# DataDriven_sheet3_power_supply.net
KiCad netlist of a schematic drawn in Altium Designer
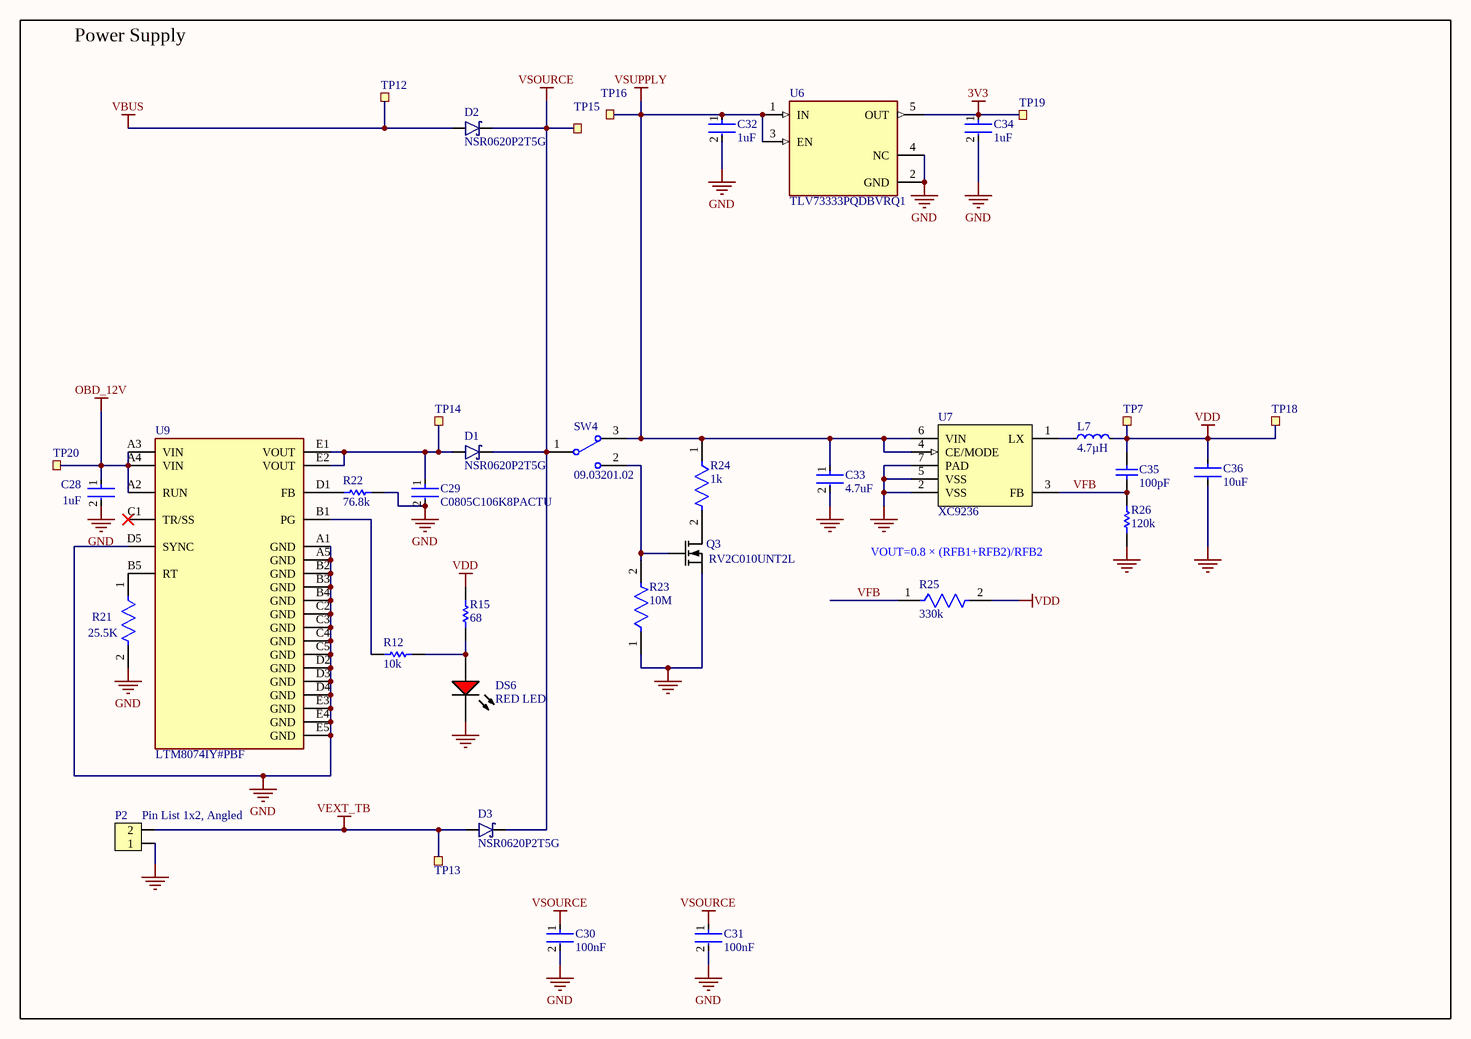
[diagram p0: DataDriven_sheet3_power_supply.SchDoc]

(export (version "E")
  (design (tool "Eeschema 10.0.6"))
  (components
    (comp (ref "C28")
      (value "1uF")
      (footprint "FP-0603-L_1_6_0_1-W_0_8_0-IPC_A")
      (description "1 µF ±10% 50V Ceramic Capacitor X5R 0603 (1608 Metric)")
      (fields (field (name "TOLERANCE") "10%") (field (name "MANUFACTURER") "Taiyo Yuden"))
      (libsource (lib "Altium Content Vault") (part "02cd4be3c70576c341d710602a673aa"))
    )
    (comp (ref "C29")
      (value "C0805C106K8PACTU")
      (footprint "FP-C0805C-DG-MFG")
      (description "CAP CER 10UF 10V X5R 0805")
      (fields (field (name "TOLERANCE") "10%") (field (name "MANUFACTURER") "Kemet"))
      (libsource (lib "Altium Content Vault") (part "11868f565c42a9108669ba33697ecf6"))
    )
    (comp (ref "C30")
      (value "100nF")
      (footprint "FP-CGA3E-0_3-0_1-IPC_A")
      (description "Cap Ceramic 100nF 50V X7R 10% Pad SMD 0603 +125°C Automotive T/R")
      (fields (field (name "TOLERANCE") "10%") (field (name "VOLTAGE") "50V"))
      (libsource (lib "Altium Content Vault") (part "b4654b650e69147ec39a6b967a45e02"))
    )
    (comp (ref "C31")
      (value "100nF")
      (footprint "FP-CGA3E-0_3-0_1-IPC_A")
      (description "Cap Ceramic 100nF 50V X7R 10% Pad SMD 0603 +125°C Automotive T/R")
      (fields (field (name "TOLERANCE") "10%") (field (name "VOLTAGE") "50V"))
      (libsource (lib "Altium Content Vault") (part "b4654b650e69147ec39a6b967a45e02"))
    )
    (comp (ref "C32")
      (value "1uF")
      (footprint "FP-GRT188-0_1-e0_2_0_5-IPC_B")
      (description "Multi-Layer Ceramic Capacitor 1uF 50V X5R ±10% 0603 Paper T/R")
      (fields (field (name "TOLERANCE") "10%") (field (name "MANUFACTURER") "Murata"))
      (libsource (lib "Altium Content Vault") (part "02cd4be3c70576c341d710602a673aa"))
    )
    (comp (ref "C33")
      (value "4.7uF")
      (footprint "FP-GRM188-0_2-IPC_C")
      (description "Chip Multilayer Ceramic Capacitors for General Purpose, 0603, 4.7uF, X5R, 15%, 10%, 35V")
      (fields (field (name "VOLTAGE") "35V") (field (name "TOLERANCE") "10%"))
      (libsource (lib "Altium Content Vault") (part "11868f565c42a9108669ba33697ecf6"))
    )
    (comp (ref "C34")
      (value "1uF")
      (footprint "FP-GRT188-0_1-e0_2_0_5-IPC_B")
      (description "Multi-Layer Ceramic Capacitor 1uF 50V X5R ±10% 0603 Paper T/R")
      (fields (field (name "TOLERANCE") "10%") (field (name "MANUFACTURER") "Murata"))
      (libsource (lib "Altium Content Vault") (part "02cd4be3c70576c341d710602a673aa"))
    )
    (comp (ref "C35")
      (value "100pF")
      (footprint "CAPC1608X90X40ML10T20")
      (description "Chip Capacitor, 100 pF, +/- 5%, 50 V, -55 to 125 degC, 0603 (1608 Metric), RoHS, Tape and Reel")
      (fields (field (name "TOLERANCE") "5%") (field (name "VOLTAGE") "50V"))
      (libsource (lib "Altium Content Vault") (part "CAP-NP-2"))
    )
    (comp (ref "C36")
      (value "10uF")
      (footprint "FP-CL10-IPC_C")
      (description "Cap Ceramic 10uF 25V X5R ±20% Pad SMD 0603 +85°C T/R")
      (fields (field (name "TOLERANCE") "20%") (field (name "MANUFACTURER") "Samsung"))
      (libsource (lib "") (part "b4654b650e69147ec39a6b967a45e02_1"))
    )
    (comp (ref "D1")
      (value "NSR0620P2T5G")
      (footprint "SODFL100X40-2N")
      (description "20V schottky barrier diode, Vf 350 mV @ 100 mA, Ir 2.0 µA @ 10 V, If 500 mA")
      (fields (field (name "MANUFACTURER") "ON Semiconductor") (field (name "AUTHOR") "rsk"))
      (libsource (lib "pca10090") (part "NSR0620P2T5G"))
    )
    (comp (ref "D2")
      (value "NSR0620P2T5G")
      (footprint "SODFL100X40-2N")
      (description "20V schottky barrier diode, Vf 350 mV @ 100 mA, Ir 2.0 µA @ 10 V, If 500 mA")
      (fields (field (name "MANUFACTURER") "ON Semiconductor") (field (name "AUTHOR") "rsk"))
      (libsource (lib "pca10090") (part "NSR0620P2T5G"))
    )
    (comp (ref "D3")
      (value "NSR0620P2T5G")
      (footprint "SODFL100X40-2N")
      (description "20V schottky barrier diode, Vf 350 mV @ 100 mA, Ir 2.0 µA @ 10 V, If 500 mA")
      (fields (field (name "MANUFACTURER") "ON Semiconductor") (field (name "AUTHOR") "rsk"))
      (libsource (lib "pca10090") (part "NSR0620P2T5G"))
    )
    (comp (ref "DS6")
      (value "RED LED")
      (footprint "VISH-TLMX1100_V")
      (description "LED, RED, 2.1 V, -40 to 100 degC, 2-Pin SMD (0603), RoHS, Tape and Reel")
      (fields (field (name "TOLERANCE") "5%") (field (name "MANUFACTURER") "Vishay"))
      (libsource (lib "Altium Content Vault") (part "LED-RED-AK-2"))
    )
    (comp (ref "L7")
      (value "4.7µH")
      (footprint "pca10090:TY-NR3015")
      (description "Ferrite Inductor, Shielded, 1,04A, 144mOhm")
      (fields
        (field (name "PART NUMBER") "NR3015-4µ7-1.04A-144mOhm")
        (field (name "MANUFACTURER") "Taiyo Yuden")
        (field (name "AUTHOR") "rsk")
      )
      (libsource (lib "AltiumLib") (part "IND"))
    )
    (comp (ref "P2")
      (value "Pin List 1x2, Angled")
      (footprint "pca10090:LIST_ANG_1x2-SMD-2.54MM")
      (description "Pin List 1x2, 2.54mm (100mil), Right Angled, SMD")
      (fields
        (field (name "PART NUMBER") "Pin List Ang 1x2 SMD, 2.54mm")
        (field (name "MANUFACTURER") "W-CON")
        (field (name "AUTHOR") "rsk")
      )
      (libsource (lib "AltiumLib") (part "CONN-2"))
    )
    (comp (ref "Q3")
      (value "RV2C010UNT2L")
      (footprint "pca10090:DFN65P100X40-3L")
      (description "N-Channel MOSFET, 20V, 1A, 470mOhm, 400mW")
      (fields (field (name "MANUFACTURER") "Rohm Semiconductor") (field (name "AUTHOR") "rsk"))
      (libsource (lib "AltiumLib") (part "T{colon}FET-N"))
    )
    (comp (ref "R12")
      (value "10k")
      (footprint "RESC1609X50X30NL8T20")
      (description "Chip Resistor, 10 KOhm, +/- 1%, 100 mW, -55 to 155 degC, 0603 (1608 Metric), RoHS, Tape and Reel")
      (fields
        (field (name "MANUFACTURER") "Vishay Semiconductor")
        (field (name "MANUFACTURER PART NUMBER") "Vishay")
      )
      (libsource (lib "Altium Content Vault") (part "RES-2"))
    )
    (comp (ref "R15")
      (value "68")
      (footprint "RESC1608X55X30ML15T15")
      (description "68 Ohms ±1% 0.1W, 1/10W Chip Resistor 0603 (1608 Metric) Automotive AEC-Q200 Thick Film")
      (fields (field (name "MANUFACTURER") "Panasonic") (field (name "PART NUMBER") "ERJ3EKF68R0V"))
      (libsource (lib "Altium Content Vault") (part "RES"))
    )
    (comp (ref "R21")
      (value "25.5K")
      (footprint "FP-CRCW0603-e3-IPC_A")
      (description "RES Thick Film, 25.5kΩ, 1%, 0.1W, 100ppm/°C, 0603")
      (fields (field (name "TOLERANCE") "1%") (field (name "MANUFACTURER") "Vishay"))
      (libsource (lib "Altium Content Vault") (part "1029c3af85768c4190bb7ad29bc67b5"))
    )
    (comp (ref "R22")
      (value "76.8k")
      (footprint "RESC1609X50X30ML10T20")
      (description "76.8 kOhms ±1% 0.1W, 1/10W Chip Resistor 0603 (1608 Metric) Automotive AEC-Q200 Thick Film")
      (fields (field (name "PART NUMBER") "CRCW060376K8FKEA") (field (name "MANUFACTURER") "Vishay Dale"))
      (libsource (lib "Altium Content Vault") (part "RES"))
    )
    (comp (ref "R23")
      (value "10M")
      (footprint "FP-RMCF0603-IPC_A")
      (description "10MΩ ±5% 0.1W 0603 Thick Film Chip Resistor AEC-Q200 compliant")
      (fields (field (name "TOLERANCE") "5%") (field (name "MANUFACTURER") "Stackpole Electronics"))
      (libsource (lib "Altium Content Vault") (part "1029c3af85768c4190bb7ad29bc67b5"))
    )
    (comp (ref "R24")
      (value "1k")
      (footprint "FP-CRCW0603-e3-MFG")
      (description "RES Thick Film, 1kΩ, 1%, 0.1W, 100ppm/°C, 0603")
      (fields (field (name "TOLERANCE") "1%") (field (name "MANUFACTURER") "Vishay Dale"))
      (libsource (lib "Altium Content Vault") (part "1029c3af85768c4190bb7ad29bc67b5"))
    )
    (comp (ref "R25")
      (value "330k")
      (footprint "FP-CRCW0603-e3-IPC_A")
      (description "RES Thick Film, 330kΩ, 1%, 0.1W, 100ppm/°C, 0603")
      (fields (field (name "TOLERANCE") "1%") (field (name "MANUFACTURER") "Vishay"))
      (libsource (lib "Altium Content Vault") (part "1029c3af85768c4190bb7ad29bc67b5"))
    )
    (comp (ref "R26")
      (value "120k")
      (footprint "RESC1609X55X30ML15T15")
      (description "Chip Resistor, 120 KOhm, +/- 1%, 0.1 W, -55 to 155 degC, 0603 (1608 Metric), RoHS, Tape and Reel")
      (fields (field (name "TOLERANCE") "1%") (field (name "MANUFACTURER") "Panasonic"))
      (libsource (lib "Altium Content Vault") (part "RES-2"))
    )
    (comp (ref "SW4")
      (value "09.03201.02")
      (footprint "EOZ-09.03201.02-3")
      (description "PCB Switch, SPDT, 12 V, 500 mA, 6 W, -40 to 85 degC, 3-Pin THD, RoHS, Tape and Reel")
      (fields (field (name "MANUFACTURER") "EOZ") (field (name "PART NUMBER") "EAO 09.03201.02"))
      (libsource (lib "Altium Content Vault") (part "SW_SPDT-3_A"))
    )
    (comp (ref "TP7")
      (value "Ø1.5mm,SMD")
      (footprint "pca10090:TP_SMD_D1.5mm")
      (description "1.5mm circular SMD testpad")
      (fields
        (field (name "PART NUMBER") "TP_SMD_Ø1.5MM")
        (field (name "MANUFACTURER") "Nordic Semiconductor")
        (field (name "AUTHOR") "rsk")
      )
      (libsource (lib "") (part "TESTPAD_2"))
    )
    (comp (ref "TP12")
      (value "Ø1.5mm,SMD")
      (footprint "pca10090:TP_SMD_D1.5mm")
      (description "1.5mm circular SMD testpad")
      (fields
        (field (name "PART NUMBER") "TP_SMD_Ø1.5MM")
        (field (name "MANUFACTURER") "Nordic Semiconductor")
        (field (name "AUTHOR") "rsk")
      )
      (libsource (lib "") (part "TESTPAD_2"))
    )
    (comp (ref "TP13")
      (value "Ø1.5mm,SMD")
      (footprint "pca10090:TP_SMD_D1.5mm")
      (description "1.5mm circular SMD testpad")
      (fields
        (field (name "PART NUMBER") "TP_SMD_Ø1.5MM")
        (field (name "MANUFACTURER") "Nordic Semiconductor")
        (field (name "AUTHOR") "rsk")
      )
      (libsource (lib "") (part "TESTPAD_3"))
    )
    (comp (ref "TP14")
      (value "Ø1.5mm,SMD")
      (footprint "pca10090:TP_SMD_D1.5mm")
      (description "1.5mm circular SMD testpad")
      (fields
        (field (name "PART NUMBER") "TP_SMD_Ø1.5MM")
        (field (name "MANUFACTURER") "Nordic Semiconductor")
        (field (name "AUTHOR") "rsk")
      )
      (libsource (lib "") (part "TESTPAD_2"))
    )
    (comp (ref "TP15")
      (value "Ø1.5mm,SMD")
      (footprint "pca10090:TP_SMD_D1.5mm")
      (description "1.5mm circular SMD testpad")
      (fields
        (field (name "PART NUMBER") "TP_SMD_Ø1.5MM")
        (field (name "MANUFACTURER") "Nordic Semiconductor")
        (field (name "AUTHOR") "rsk")
      )
      (libsource (lib "AltiumLib") (part "TESTPAD"))
    )
    (comp (ref "TP16")
      (value "Ø1.5mm,SMD")
      (footprint "pca10090:TP_SMD_D1.5mm")
      (description "1.5mm circular SMD testpad")
      (fields
        (field (name "PART NUMBER") "TP_SMD_Ø1.5MM")
        (field (name "MANUFACTURER") "Nordic Semiconductor")
        (field (name "AUTHOR") "rsk")
      )
      (libsource (lib "") (part "TESTPAD_1"))
    )
    (comp (ref "TP18")
      (value "Ø1.5mm,SMD")
      (footprint "pca10090:TP_SMD_D1.5mm")
      (description "1.5mm circular SMD testpad")
      (fields
        (field (name "PART NUMBER") "TP_SMD_Ø1.5MM")
        (field (name "MANUFACTURER") "Nordic Semiconductor")
        (field (name "AUTHOR") "rsk")
      )
      (libsource (lib "") (part "TESTPAD_2"))
    )
    (comp (ref "TP19")
      (value "Ø1.5mm,SMD")
      (footprint "pca10090:TP_SMD_D1.5mm")
      (description "1.5mm circular SMD testpad")
      (fields
        (field (name "PART NUMBER") "TP_SMD_Ø1.5MM")
        (field (name "MANUFACTURER") "Nordic Semiconductor")
        (field (name "AUTHOR") "rsk")
      )
      (libsource (lib "AltiumLib") (part "TESTPAD"))
    )
    (comp (ref "TP20")
      (value "Ø1.5mm,SMD")
      (footprint "pca10090:TP_SMD_D1.5mm")
      (description "1.5mm circular SMD testpad")
      (fields
        (field (name "PART NUMBER") "TP_SMD_Ø1.5MM")
        (field (name "MANUFACTURER") "Nordic Semiconductor")
        (field (name "AUTHOR") "rsk")
      )
      (libsource (lib "") (part "TESTPAD_1"))
    )
    (comp (ref "U6")
      (value "TLV73333PQDBVRQ1")
      (footprint "FP-DBV0005A-MFG")
      (description "IC REG LINEAR 3.3V 300MA SOT23-5")
      (fields (field (name "MANUFACTURER") "Texas Instruments"))
      (libsource (lib "Components - 08.11.22 - 10.40") (part "CMP-04917-000347-1"))
    )
    (comp (ref "U7")
      (value "XC9236")
      (footprint "DataDriven_PCB1:USP-6C")
      (description "600mA Driver Transistor Built-In, Synchronous Step-Down DC/DC Converters")
      (fields
        (field (name "PART NUMBER") "XC9236F08CER-G")
        (field (name "MANUFACTURER") "Torex Semiconductor")
        (field (name "AUTHOR") "rsk")
      )
      (libsource (lib "DataDriven") (part "XC9236F08CER-G"))
    )
    (comp (ref "U9")
      (value "LTM8074IY#PBF")
      (footprint "FP-BGA-25-05-08-1566-MFG")
      (description "IC REG BUCK ADJ 1.2A 25BGA")
      (fields (field (name "MANUFACTURER") "Analog Devices Inc."))
      (libsource (lib "Altium Content Vault") (part "ca8f26ffa4f8fe5b48cf916261a6d66"))
    )
  )
  (nets
    (net (code "1") (name "/VFB") (class "Default")
      (node (ref "C35") (pin "1") (pinfunction "1_1") (pintype "passive"))
      (node (ref "R25") (pin "1") (pinfunction "1_1") (pintype "passive"))
      (node (ref "R26") (pin "2") (pinfunction "2_2") (pintype "passive"))
      (node (ref "U7") (pin "3") (pinfunction "FB_3") (pintype "power_in"))
    )
    (net (code "2") (name "3V3") (class "Default")
      (node (ref "C34") (pin "1") (pinfunction "1_1") (pintype "passive"))
      (node (ref "TP19") (pin "1") (pinfunction "1_1") (pintype "passive"))
      (node (ref "U6") (pin "5") (pinfunction "OUT_5") (pintype "output"))
    )
    (net (code "3") (name "GND") (class "Default")
      (node (ref "C28") (pin "2") (pinfunction "2_2") (pintype "passive"))
      (node (ref "C29") (pin "2") (pinfunction "2_2") (pintype "passive"))
      (node (ref "C30") (pin "2") (pinfunction "2_2") (pintype "passive"))
      (node (ref "C31") (pin "2") (pinfunction "2_2") (pintype "passive"))
      (node (ref "C32") (pin "2") (pinfunction "2_2") (pintype "passive"))
      (node (ref "C33") (pin "2") (pinfunction "2_2") (pintype "passive"))
      (node (ref "C34") (pin "2") (pinfunction "2_2") (pintype "passive"))
      (node (ref "C36") (pin "2") (pinfunction "2_2") (pintype "passive"))
      (node (ref "DS6") (pin "2") (pinfunction "K_2") (pintype "passive"))
      (node (ref "P2") (pin "1") (pinfunction "1_1") (pintype "passive"))
      (node (ref "Q3") (pin "2") (pinfunction "S_2") (pintype "passive"))
      (node (ref "R21") (pin "2") (pinfunction "2_2") (pintype "passive"))
      (node (ref "R22") (pin "2") (pinfunction "2_2") (pintype "passive"))
      (node (ref "R23") (pin "1") (pinfunction "1_1") (pintype "passive"))
      (node (ref "R26") (pin "1") (pinfunction "1_1") (pintype "passive"))
      (node (ref "U6") (pin "2") (pinfunction "GND_2") (pintype "power_in"))
      (node (ref "U6") (pin "4") (pinfunction "NC_4") (pintype "passive"))
      (node (ref "U7") (pin "2") (pinfunction "VSS_2") (pintype "power_in"))
      (node (ref "U7") (pin "5") (pinfunction "VSS_5") (pintype "power_in"))
      (node (ref "U7") (pin "7") (pinfunction "PAD_7") (pintype "power_in"))
      (node (ref "U9") (pin "A1") (pinfunction "GND_A1") (pintype "power_in"))
      (node (ref "U9") (pin "A5") (pinfunction "GND_A5") (pintype "power_in"))
      (node (ref "U9") (pin "B2") (pinfunction "GND_B2") (pintype "power_in"))
      (node (ref "U9") (pin "B3") (pinfunction "GND_B3") (pintype "power_in"))
      (node (ref "U9") (pin "B4") (pinfunction "GND_B4") (pintype "power_in"))
      (node (ref "U9") (pin "C2") (pinfunction "GND_C2") (pintype "power_in"))
      (node (ref "U9") (pin "C3") (pinfunction "GND_C3") (pintype "power_in"))
      (node (ref "U9") (pin "C4") (pinfunction "GND_C4") (pintype "power_in"))
      (node (ref "U9") (pin "C5") (pinfunction "GND_C5") (pintype "power_in"))
      (node (ref "U9") (pin "D2") (pinfunction "GND_D2") (pintype "power_in"))
      (node (ref "U9") (pin "D3") (pinfunction "GND_D3") (pintype "power_in"))
      (node (ref "U9") (pin "D4") (pinfunction "GND_D4") (pintype "power_in"))
      (node (ref "U9") (pin "D5") (pinfunction "SYNC_D5") (pintype "passive"))
      (node (ref "U9") (pin "E3") (pinfunction "GND_E3") (pintype "power_in"))
      (node (ref "U9") (pin "E4") (pinfunction "GND_E4") (pintype "power_in"))
      (node (ref "U9") (pin "E5") (pinfunction "GND_E5") (pintype "power_in"))
    )
    (net (code "4") (name "Net-(D1-A)") (class "Default")
      (node (ref "C29") (pin "1") (pinfunction "1_1") (pintype "passive"))
      (node (ref "D1") (pin "2") (pinfunction "A_2") (pintype "passive"))
      (node (ref "TP14") (pin "1") (pinfunction "1_1") (pintype "passive"))
      (node (ref "U9") (pin "E1") (pinfunction "VOUT_E1") (pintype "power_in"))
      (node (ref "U9") (pin "E2") (pinfunction "VOUT_E2") (pintype "power_in"))
    )
    (net (code "5") (name "Net-(DS6-A)") (class "Default")
      (node (ref "DS6") (pin "1") (pinfunction "A_1") (pintype "passive"))
      (node (ref "R12") (pin "2") (pinfunction "2_2") (pintype "passive"))
      (node (ref "R15") (pin "1") (pinfunction "1_1") (pintype "passive"))
    )
    (net (code "6") (name "Net-(Q3-D)") (class "Default")
      (node (ref "Q3") (pin "3") (pinfunction "D_3") (pintype "passive"))
      (node (ref "R24") (pin "2") (pinfunction "2_2") (pintype "passive"))
    )
    (net (code "7") (name "Net-(Q3-G)") (class "Default")
      (node (ref "Q3") (pin "1") (pinfunction "G_1") (pintype "passive"))
      (node (ref "R23") (pin "2") (pinfunction "2_2") (pintype "passive"))
      (node (ref "SW4") (pin "2") (pinfunction "2_2") (pintype "passive"))
    )
    (net (code "8") (name "Net-(U7-LX)") (class "Default")
      (node (ref "L7") (pin "1") (pinfunction "1_1") (pintype "passive"))
      (node (ref "U7") (pin "1") (pinfunction "LX_1") (pintype "passive"))
    )
    (net (code "9") (name "Net-(U9-FB)") (class "Default")
      (node (ref "R22") (pin "1") (pinfunction "1_1") (pintype "passive"))
      (node (ref "U9") (pin "D1") (pinfunction "FB_D1") (pintype "passive"))
    )
    (net (code "10") (name "Net-(U9-PG)") (class "Default")
      (node (ref "R12") (pin "1") (pinfunction "1_1") (pintype "passive"))
      (node (ref "U9") (pin "B1") (pinfunction "PG_B1") (pintype "open_collector"))
    )
    (net (code "11") (name "Net-(U9-RT)") (class "Default")
      (node (ref "R21") (pin "1") (pinfunction "1_1") (pintype "passive"))
      (node (ref "U9") (pin "B5") (pinfunction "RT_B5") (pintype "passive"))
    )
    (net (code "12") (name "OBD_12V") (class "Default")
      (node (ref "C28") (pin "1") (pinfunction "1_1") (pintype "passive"))
      (node (ref "TP20") (pin "1") (pinfunction "1_1") (pintype "passive"))
      (node (ref "U9") (pin "A2") (pinfunction "RUN_A2") (pintype "passive"))
      (node (ref "U9") (pin "A3") (pinfunction "VIN_A3") (pintype "power_in"))
      (node (ref "U9") (pin "A4") (pinfunction "VIN_A4") (pintype "power_in"))
    )
    (net (code "13") (name "VBUS") (class "Default")
      (node (ref "D2") (pin "2") (pinfunction "A_2") (pintype "passive"))
      (node (ref "TP12") (pin "1") (pinfunction "1_1") (pintype "passive"))
    )
    (net (code "14") (name "VDD") (class "Default")
      (node (ref "C35") (pin "2") (pinfunction "2_2") (pintype "passive"))
      (node (ref "C36") (pin "1") (pinfunction "1_1") (pintype "passive"))
      (node (ref "L7") (pin "2") (pinfunction "2_2") (pintype "passive"))
      (node (ref "R15") (pin "2") (pinfunction "2_2") (pintype "passive"))
      (node (ref "R25") (pin "2") (pinfunction "2_2") (pintype "passive"))
      (node (ref "TP18") (pin "1") (pinfunction "1_1") (pintype "passive"))
      (node (ref "TP7") (pin "1") (pinfunction "1_1") (pintype "passive"))
    )
    (net (code "15") (name "VEXT_TB") (class "Default")
      (node (ref "D3") (pin "2") (pinfunction "A_2") (pintype "passive"))
      (node (ref "P2") (pin "2") (pinfunction "2_2") (pintype "passive"))
      (node (ref "TP13") (pin "1") (pinfunction "1_1") (pintype "passive"))
    )
    (net (code "16") (name "VSOURCE") (class "Default")
      (node (ref "C30") (pin "1") (pinfunction "1_1") (pintype "passive"))
      (node (ref "C31") (pin "1") (pinfunction "1_1") (pintype "passive"))
      (node (ref "D1") (pin "1") (pinfunction "C_1") (pintype "passive"))
      (node (ref "D2") (pin "1") (pinfunction "C_1") (pintype "passive"))
      (node (ref "D3") (pin "1") (pinfunction "C_1") (pintype "passive"))
      (node (ref "SW4") (pin "1") (pinfunction "1_1") (pintype "passive"))
      (node (ref "TP15") (pin "1") (pinfunction "1_1") (pintype "passive"))
    )
    (net (code "17") (name "VSUPPLY") (class "Default")
      (node (ref "C32") (pin "1") (pinfunction "1_1") (pintype "passive"))
      (node (ref "C33") (pin "1") (pinfunction "1_1") (pintype "passive"))
      (node (ref "R24") (pin "1") (pinfunction "1_1") (pintype "passive"))
      (node (ref "SW4") (pin "3") (pinfunction "3_3") (pintype "passive"))
      (node (ref "TP16") (pin "1") (pinfunction "1_1") (pintype "passive"))
      (node (ref "U6") (pin "1") (pinfunction "IN_1") (pintype "input"))
      (node (ref "U6") (pin "3") (pinfunction "EN_3") (pintype "input"))
      (node (ref "U7") (pin "4") (pinfunction "CE/MODE_4") (pintype "input"))
      (node (ref "U7") (pin "6") (pinfunction "VIN_6") (pintype "power_in"))
    )
    (net (code "18") (name "unconnected-(U9-TR{slash}SS-PadC1)") (class "Default")
      (node (ref "U9") (pin "C1") (pinfunction "TR/SS_C1") (pintype "passive+no_connect"))
    )
  )
)
